# adapter18.net
KiCad netlist of a schematic drawn in EAGLE
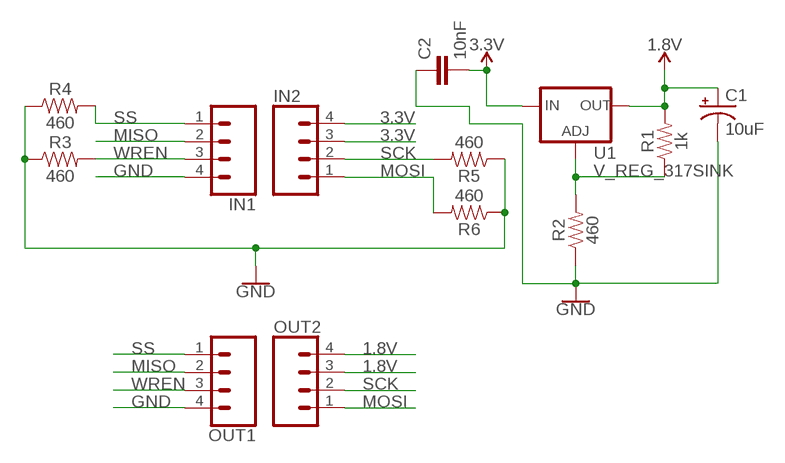
[diagram p0: schematic, sheet 1]

(export (version "E")
  (design (tool "Eeschema 10.0.6"))
  (components
    (comp (ref "C1")
      (value "10uF")
      (footprint "eagle-import:CPOL-RADIAL-2.5MM-5MM")
      (libsource (lib "eagle-import") (part "10UF-POLAR-RADIAL-2.5MM-25V-20%"))
    )
    (comp (ref "C2")
      (value "10nF")
      (footprint "eagle-import:CAP-PTH-10MM")
      (libsource (lib "eagle-import") (part "10NF-PTH-10MM-10000V-1-%"))
    )
    (comp (ref "IN1")
      (value "CONN_04")
      (footprint "eagle-import:1X04")
      (libsource (lib "eagle-import") (part "CONN_04"))
    )
    (comp (ref "IN2")
      (value "CONN_04")
      (footprint "eagle-import:1X04")
      (libsource (lib "eagle-import") (part "CONN_04"))
    )
    (comp (ref "OUT1")
      (value "CONN_04")
      (footprint "eagle-import:1X04")
      (libsource (lib "eagle-import") (part "CONN_04"))
    )
    (comp (ref "OUT2")
      (value "CONN_04")
      (footprint "eagle-import:1X04")
      (libsource (lib "eagle-import") (part "CONN_04"))
    )
    (comp (ref "R1")
      (value "1k")
      (footprint "eagle-import:AXIAL-0.3")
      (libsource (lib "eagle-import") (part "1KOHM-HORIZ-1/4W-1%"))
    )
    (comp (ref "R2")
      (value "460")
      (footprint "eagle-import:AXIAL-0.3")
      (libsource (lib "eagle-import") (part "1KOHM-HORIZ-1/4W-1%"))
    )
    (comp (ref "R3")
      (value "460")
      (footprint "eagle-import:AXIAL-0.3")
      (libsource (lib "eagle-import") (part "1KOHM-HORIZ-1/4W-1%"))
    )
    (comp (ref "R4")
      (value "460")
      (footprint "eagle-import:AXIAL-0.3")
      (libsource (lib "eagle-import") (part "1KOHM-HORIZ-1/4W-1%"))
    )
    (comp (ref "R5")
      (value "460")
      (footprint "eagle-import:AXIAL-0.3")
      (libsource (lib "eagle-import") (part "1KOHM-HORIZ-1/4W-1%"))
    )
    (comp (ref "R6")
      (value "460")
      (footprint "eagle-import:AXIAL-0.3")
      (libsource (lib "eagle-import") (part "1KOHM-HORIZ-1/4W-1%"))
    )
    (comp (ref "U1")
      (value "V_REG_317SINK")
      (footprint "eagle-import:TO220-ADJ")
      (libsource (lib "eagle-import") (part "V_REG_317SINK"))
    )
  )
  (nets
    (net (code "1") (name "/MISO") (class "Default")
      (node (ref "IN1") (pin "2") (pinfunction "2_2") (pintype "passive"))
      (node (ref "OUT1") (pin "2") (pinfunction "2_2") (pintype "passive"))
    )
    (net (code "2") (name "/MOSI") (class "Default")
      (node (ref "IN2") (pin "1") (pinfunction "1_1") (pintype "passive"))
      (node (ref "OUT2") (pin "1") (pinfunction "1_1") (pintype "passive"))
      (node (ref "R6") (pin "P$2") (pinfunction "2_P$2") (pintype "passive"))
    )
    (net (code "3") (name "/SCK") (class "Default")
      (node (ref "IN2") (pin "2") (pinfunction "2_2") (pintype "passive"))
      (node (ref "OUT2") (pin "2") (pinfunction "2_2") (pintype "passive"))
      (node (ref "R5") (pin "P$2") (pinfunction "2_P$2") (pintype "passive"))
    )
    (net (code "4") (name "/SS") (class "Default")
      (node (ref "IN1") (pin "1") (pinfunction "1_1") (pintype "passive"))
      (node (ref "OUT1") (pin "1") (pinfunction "1_1") (pintype "passive"))
      (node (ref "R4") (pin "P$2") (pinfunction "2_P$2") (pintype "passive"))
    )
    (net (code "5") (name "/WREN") (class "Default")
      (node (ref "IN1") (pin "3") (pinfunction "3_3") (pintype "passive"))
      (node (ref "OUT1") (pin "3") (pinfunction "3_3") (pintype "passive"))
      (node (ref "R3") (pin "P$2") (pinfunction "2_P$2") (pintype "passive"))
    )
    (net (code "6") (name "1.8V") (class "Default")
      (node (ref "C1") (pin "1") (pinfunction "+_1") (pintype "passive"))
      (node (ref "OUT2") (pin "3") (pinfunction "3_3") (pintype "passive"))
      (node (ref "OUT2") (pin "4") (pinfunction "4_4") (pintype "passive"))
      (node (ref "R1") (pin "P$2") (pinfunction "2_P$2") (pintype "passive"))
      (node (ref "U1") (pin "OUT") (pinfunction "OUT_OUT") (pintype "output"))
    )
    (net (code "7") (name "3.3V") (class "Default")
      (node (ref "C2") (pin "2") (pinfunction "2_2") (pintype "passive"))
      (node (ref "IN2") (pin "3") (pinfunction "3_3") (pintype "passive"))
      (node (ref "IN2") (pin "4") (pinfunction "4_4") (pintype "passive"))
      (node (ref "U1") (pin "IN") (pinfunction "IN_IN") (pintype "input"))
    )
    (net (code "8") (name "GND") (class "Default")
      (node (ref "C1") (pin "2") (pinfunction "-_2") (pintype "passive"))
      (node (ref "C2") (pin "1") (pinfunction "1_1") (pintype "passive"))
      (node (ref "IN1") (pin "4") (pinfunction "4_4") (pintype "passive"))
      (node (ref "OUT1") (pin "4") (pinfunction "4_4") (pintype "passive"))
      (node (ref "R2") (pin "P$1") (pinfunction "1_P$1") (pintype "passive"))
      (node (ref "R3") (pin "P$1") (pinfunction "1_P$1") (pintype "passive"))
      (node (ref "R4") (pin "P$1") (pinfunction "1_P$1") (pintype "passive"))
      (node (ref "R5") (pin "P$1") (pinfunction "1_P$1") (pintype "passive"))
      (node (ref "R6") (pin "P$1") (pinfunction "1_P$1") (pintype "passive"))
    )
    (net (code "9") (name "Net-(R1-1)") (class "Default")
      (node (ref "R1") (pin "P$1") (pinfunction "1_P$1") (pintype "passive"))
      (node (ref "R2") (pin "P$2") (pinfunction "2_P$2") (pintype "passive"))
      (node (ref "U1") (pin "ADJ") (pinfunction "ADJ_ADJ") (pintype "input"))
    )
  )
)
